# sensor_board_001b.net
KiCad netlist of a schematic drawn in EAGLE
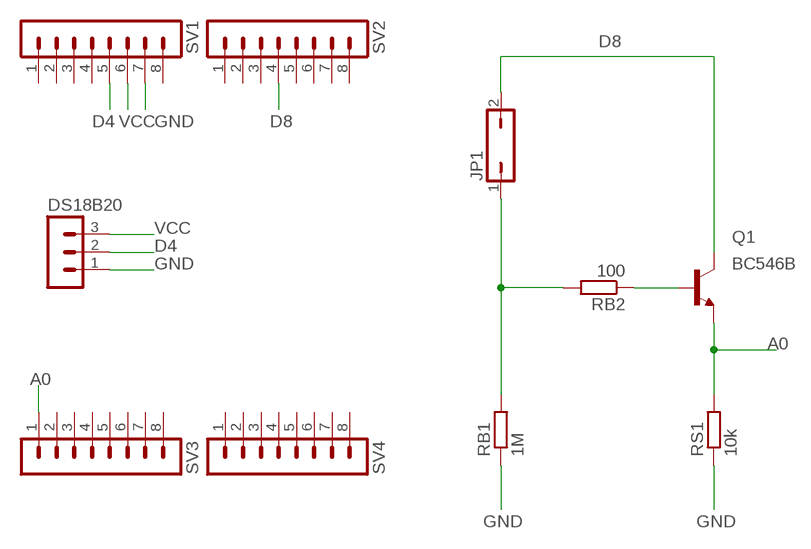
[diagram p0: schematic, sheet 1]

(export (version "E")
  (design (tool "Eeschema 10.0.6"))
  (components
    (comp (ref "DS18B20")
      (value "MA03-1")
      (footprint "eagle-import:MA03-1")
      (libsource (lib "eagle-import") (part "MA03-1"))
    )
    (comp (ref "JP1")
      (value "JP1Q")
      (footprint "eagle-import:JP1")
      (libsource (lib "eagle-import") (part "JP1Q"))
    )
    (comp (ref "Q1")
      (value "BC546B")
      (footprint "eagle-import:TO92-EBC")
      (libsource (lib "eagle-import") (part "BC546B"))
    )
    (comp (ref "RB1")
      (value "1M")
      (footprint "eagle-import:0204_5")
      (libsource (lib "eagle-import") (part "R-EU_0204/5"))
    )
    (comp (ref "RB2")
      (value "100")
      (footprint "eagle-import:0204V")
      (libsource (lib "eagle-import") (part "R-EU_0204/2V"))
    )
    (comp (ref "RS1")
      (value "10k")
      (footprint "eagle-import:0204_7")
      (libsource (lib "eagle-import") (part "R-EU_0204/7"))
    )
    (comp (ref "SV1")
      (value "MA08-1")
      (footprint "eagle-import:MA08-1")
      (libsource (lib "eagle-import") (part "MA08-1"))
    )
    (comp (ref "SV2")
      (value "MA08-1")
      (footprint "eagle-import:MA08-1")
      (libsource (lib "eagle-import") (part "MA08-1"))
    )
    (comp (ref "SV3")
      (value "MA08-1")
      (footprint "eagle-import:MA08-1")
      (libsource (lib "eagle-import") (part "MA08-1"))
    )
    (comp (ref "SV4")
      (value "MA08-1")
      (footprint "eagle-import:MA08-1")
      (libsource (lib "eagle-import") (part "MA08-1"))
    )
  )
  (nets
    (net (code "1") (name "/A0") (class "Default")
      (node (ref "Q1") (pin "E") (pinfunction "E_E") (pintype "passive"))
      (node (ref "RS1") (pin "2") (pinfunction "2_2") (pintype "passive"))
      (node (ref "SV3") (pin "1") (pinfunction "1_1") (pintype "passive"))
    )
    (net (code "2") (name "/D4") (class "Default")
      (node (ref "DS18B20") (pin "2") (pinfunction "2_2") (pintype "passive"))
      (node (ref "SV1") (pin "5") (pinfunction "5_5") (pintype "passive"))
    )
    (net (code "3") (name "/D8") (class "Default")
      (node (ref "JP1") (pin "2") (pinfunction "2_2") (pintype "passive"))
      (node (ref "Q1") (pin "C") (pinfunction "C_C") (pintype "passive"))
      (node (ref "SV2") (pin "4") (pinfunction "4_4") (pintype "passive"))
    )
    (net (code "4") (name "/GND") (class "Default")
      (node (ref "DS18B20") (pin "1") (pinfunction "1_1") (pintype "passive"))
      (node (ref "RB1") (pin "1") (pinfunction "1_1") (pintype "passive"))
      (node (ref "RS1") (pin "1") (pinfunction "1_1") (pintype "passive"))
      (node (ref "SV1") (pin "7") (pinfunction "7_7") (pintype "passive"))
    )
    (net (code "5") (name "/VCC") (class "Default")
      (node (ref "DS18B20") (pin "3") (pinfunction "3_3") (pintype "passive"))
      (node (ref "SV1") (pin "6") (pinfunction "6_6") (pintype "passive"))
    )
    (net (code "6") (name "Net-(JP1-Pad1)") (class "Default")
      (node (ref "JP1") (pin "1") (pinfunction "1_1") (pintype "passive"))
      (node (ref "RB1") (pin "2") (pinfunction "2_2") (pintype "passive"))
      (node (ref "RB2") (pin "2") (pinfunction "2_2") (pintype "passive"))
    )
    (net (code "7") (name "Net-(Q1-PadB)") (class "Default")
      (node (ref "Q1") (pin "B") (pinfunction "B_B") (pintype "passive"))
      (node (ref "RB2") (pin "1") (pinfunction "1_1") (pintype "passive"))
    )
    (net (code "8") (name "unconnected-(SV1-Pad1)") (class "Default")
      (node (ref "SV1") (pin "1") (pinfunction "1_1") (pintype "passive"))
    )
    (net (code "9") (name "unconnected-(SV1-Pad2)") (class "Default")
      (node (ref "SV1") (pin "2") (pinfunction "2_2") (pintype "passive"))
    )
    (net (code "10") (name "unconnected-(SV1-Pad3)") (class "Default")
      (node (ref "SV1") (pin "3") (pinfunction "3_3") (pintype "passive"))
    )
    (net (code "11") (name "unconnected-(SV1-Pad4)") (class "Default")
      (node (ref "SV1") (pin "4") (pinfunction "4_4") (pintype "passive"))
    )
    (net (code "12") (name "unconnected-(SV1-Pad8)") (class "Default")
      (node (ref "SV1") (pin "8") (pinfunction "8_8") (pintype "passive"))
    )
    (net (code "13") (name "unconnected-(SV2-Pad1)") (class "Default")
      (node (ref "SV2") (pin "1") (pinfunction "1_1") (pintype "passive"))
    )
    (net (code "14") (name "unconnected-(SV2-Pad2)") (class "Default")
      (node (ref "SV2") (pin "2") (pinfunction "2_2") (pintype "passive"))
    )
    (net (code "15") (name "unconnected-(SV2-Pad3)") (class "Default")
      (node (ref "SV2") (pin "3") (pinfunction "3_3") (pintype "passive"))
    )
    (net (code "16") (name "unconnected-(SV2-Pad5)") (class "Default")
      (node (ref "SV2") (pin "5") (pinfunction "5_5") (pintype "passive"))
    )
    (net (code "17") (name "unconnected-(SV2-Pad6)") (class "Default")
      (node (ref "SV2") (pin "6") (pinfunction "6_6") (pintype "passive"))
    )
    (net (code "18") (name "unconnected-(SV2-Pad7)") (class "Default")
      (node (ref "SV2") (pin "7") (pinfunction "7_7") (pintype "passive"))
    )
    (net (code "19") (name "unconnected-(SV2-Pad8)") (class "Default")
      (node (ref "SV2") (pin "8") (pinfunction "8_8") (pintype "passive"))
    )
    (net (code "20") (name "unconnected-(SV3-Pad2)") (class "Default")
      (node (ref "SV3") (pin "2") (pinfunction "2_2") (pintype "passive"))
    )
    (net (code "21") (name "unconnected-(SV3-Pad3)") (class "Default")
      (node (ref "SV3") (pin "3") (pinfunction "3_3") (pintype "passive"))
    )
    (net (code "22") (name "unconnected-(SV3-Pad4)") (class "Default")
      (node (ref "SV3") (pin "4") (pinfunction "4_4") (pintype "passive"))
    )
    (net (code "23") (name "unconnected-(SV3-Pad5)") (class "Default")
      (node (ref "SV3") (pin "5") (pinfunction "5_5") (pintype "passive"))
    )
    (net (code "24") (name "unconnected-(SV3-Pad6)") (class "Default")
      (node (ref "SV3") (pin "6") (pinfunction "6_6") (pintype "passive"))
    )
    (net (code "25") (name "unconnected-(SV3-Pad7)") (class "Default")
      (node (ref "SV3") (pin "7") (pinfunction "7_7") (pintype "passive"))
    )
    (net (code "26") (name "unconnected-(SV3-Pad8)") (class "Default")
      (node (ref "SV3") (pin "8") (pinfunction "8_8") (pintype "passive"))
    )
    (net (code "27") (name "unconnected-(SV4-Pad1)") (class "Default")
      (node (ref "SV4") (pin "1") (pinfunction "1_1") (pintype "passive"))
    )
    (net (code "28") (name "unconnected-(SV4-Pad2)") (class "Default")
      (node (ref "SV4") (pin "2") (pinfunction "2_2") (pintype "passive"))
    )
    (net (code "29") (name "unconnected-(SV4-Pad3)") (class "Default")
      (node (ref "SV4") (pin "3") (pinfunction "3_3") (pintype "passive"))
    )
    (net (code "30") (name "unconnected-(SV4-Pad4)") (class "Default")
      (node (ref "SV4") (pin "4") (pinfunction "4_4") (pintype "passive"))
    )
    (net (code "31") (name "unconnected-(SV4-Pad5)") (class "Default")
      (node (ref "SV4") (pin "5") (pinfunction "5_5") (pintype "passive"))
    )
    (net (code "32") (name "unconnected-(SV4-Pad6)") (class "Default")
      (node (ref "SV4") (pin "6") (pinfunction "6_6") (pintype "passive"))
    )
    (net (code "33") (name "unconnected-(SV4-Pad7)") (class "Default")
      (node (ref "SV4") (pin "7") (pinfunction "7_7") (pintype "passive"))
    )
    (net (code "34") (name "unconnected-(SV4-Pad8)") (class "Default")
      (node (ref "SV4") (pin "8") (pinfunction "8_8") (pintype "passive"))
    )
  )
)
